# xkid_0_4.net
KiCad netlist of a schematic drawn in EAGLE
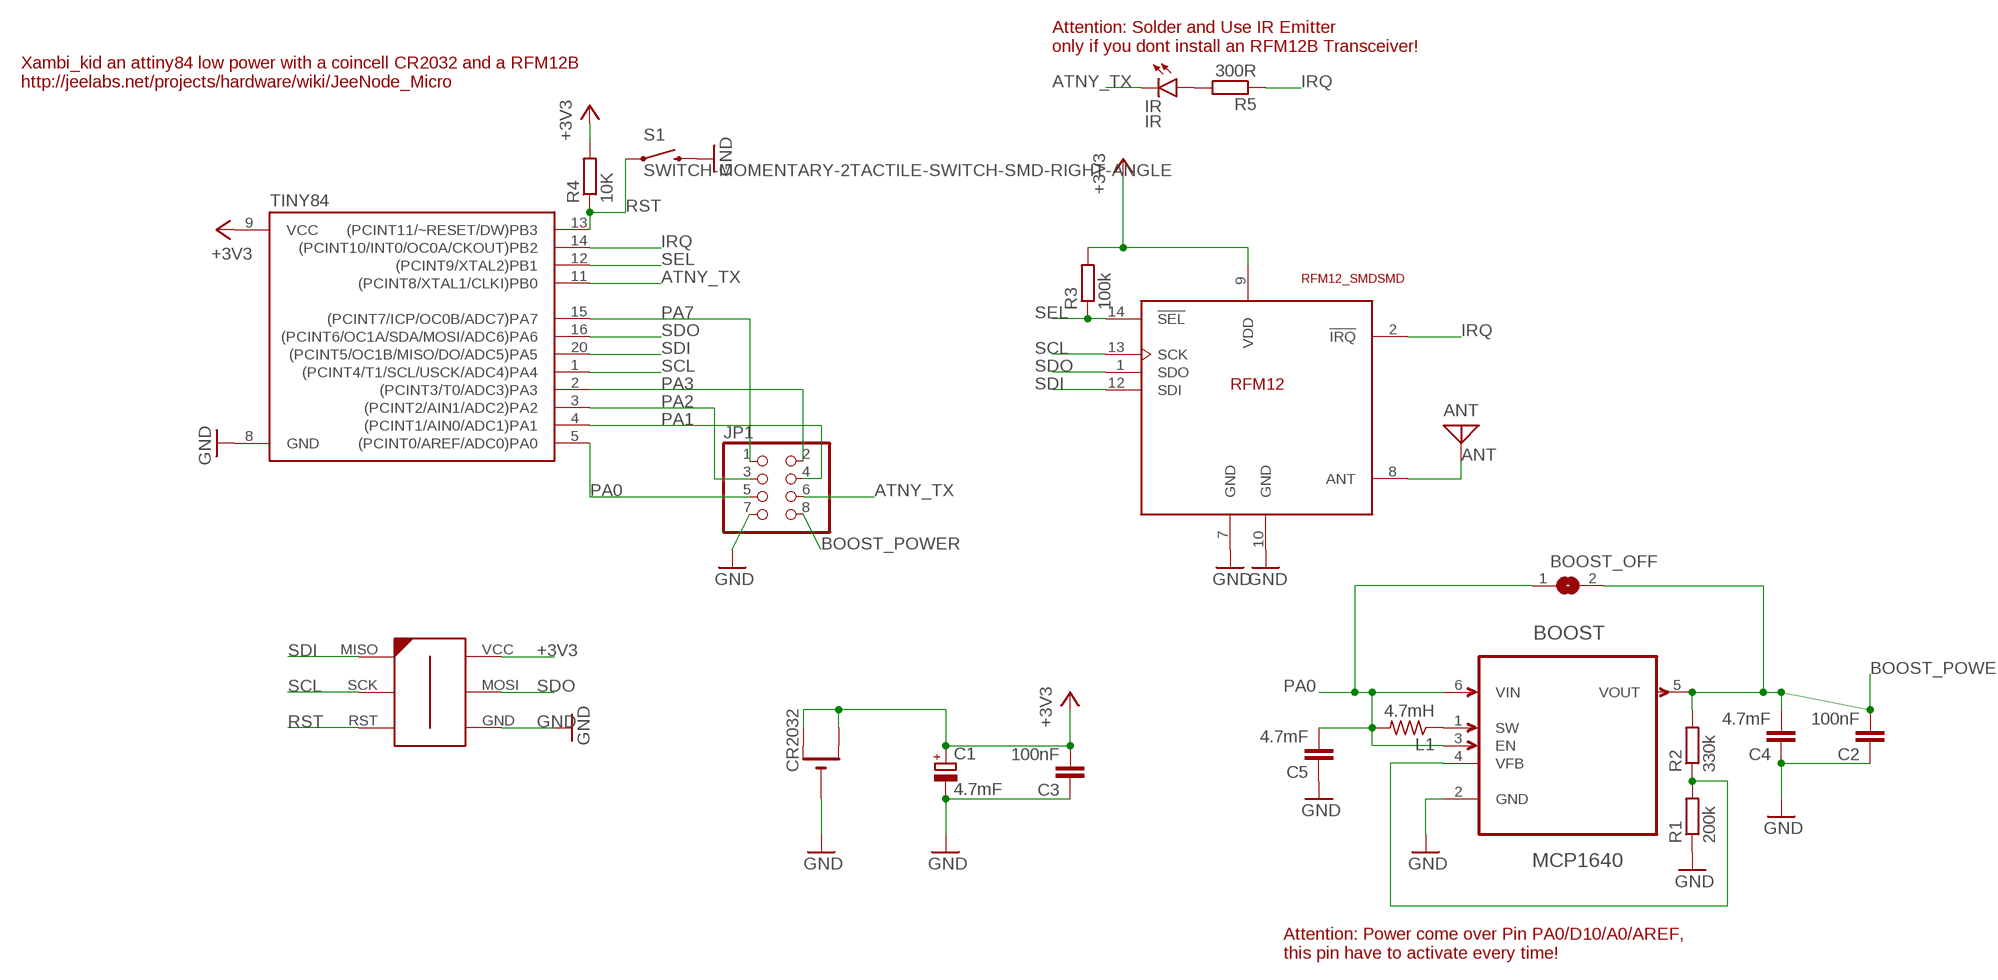
[diagram p0: schematic, sheet 1]

(export (version "E")
  (design (tool "Eeschema 10.0.6"))
  (components
    (comp (ref "ANT")
      (value "ANTENNA")
      (footprint "eagle-import:PAD-01")
      (libsource (lib "eagle-import") (part "ANTENNA"))
    )
    (comp (ref "BOOST")
      (value "MCP1640")
      (footprint "eagle-import:SOT95P270X145-6N")
      (fields (field (name "MPN") "MCP1640BT-I/CHY"))
      (libsource (lib "eagle-import") (part "MCP1640BT-I/CHY"))
    )
    (comp (ref "BOOST_OFF")
      (value "SJ")
      (footprint "eagle-import:SJ")
      (libsource (lib "eagle-import") (part "SJ"))
    )
    (comp (ref "C1")
      (value "4.7mF")
      (footprint "eagle-import:CT3216")
      (libsource (lib "eagle-import") (part "CPOL-EUCT3216"))
    )
    (comp (ref "C2")
      (value "100nF")
      (footprint "eagle-import:C0805K")
      (libsource (lib "eagle-import") (part "C-EUC0805K"))
    )
    (comp (ref "C3")
      (value "100nF")
      (footprint "eagle-import:C0805K")
      (libsource (lib "eagle-import") (part "C-EUC0805K"))
    )
    (comp (ref "C4")
      (value "4.7mF")
      (footprint "eagle-import:C0805K")
      (libsource (lib "eagle-import") (part "C-EUC0805K"))
    )
    (comp (ref "C5")
      (value "4.7mF")
      (footprint "eagle-import:C0805K")
      (libsource (lib "eagle-import") (part "C-EUC0805K"))
    )
    (comp (ref "CR2032")
      (value "CR2032SMT")
      (footprint "eagle-import:CR2032-SMD")
      (libsource (lib "eagle-import") (part "CR2032SMT"))
    )
    (comp (ref "IR")
      (value "IR")
      (footprint "eagle-import:LED3MM")
      (libsource (lib "eagle-import") (part "LED3MM"))
    )
    (comp (ref "JP1")
      (value "PINHD-2X4_2.54")
      (footprint "eagle-import:2X04")
      (libsource (lib "eagle-import") (part "PINHD-2X4_2.54"))
    )
    (comp (ref "L1")
      (value "4.7mH")
      (footprint "eagle-import:0204_5")
      (libsource (lib "eagle-import") (part "R-US_0204/5"))
    )
    (comp (ref "R1")
      (value "200k")
      (footprint "eagle-import:R0805")
      (libsource (lib "eagle-import") (part "R-EU_R0805"))
    )
    (comp (ref "R2")
      (value "330k")
      (footprint "eagle-import:R0805")
      (libsource (lib "eagle-import") (part "R-EU_R0805"))
    )
    (comp (ref "R3")
      (value "100k")
      (footprint "eagle-import:R0805")
      (libsource (lib "eagle-import") (part "R-EU_R0805"))
    )
    (comp (ref "R4")
      (value "10K")
      (footprint "eagle-import:R0805")
      (libsource (lib "eagle-import") (part "R-EU_R0805"))
    )
    (comp (ref "R5")
      (value "300R")
      (footprint "eagle-import:R0805")
      (libsource (lib "eagle-import") (part "R-EU_R0805"))
    )
    (comp (ref "S1")
      (value "SWITCH-MOMENTARY-2TACTILE-SWITCH-SMD-RIGHT-ANGLE")
      (footprint "eagle-import:TACTILE_SWITCH-SMD-RIGHT-ANGLE")
      (libsource (lib "eagle-import") (part "SWITCH-MOMENTARY-2TACTILE-SWITCH-SMD-RIGHT-ANGLE"))
    )
    (comp (ref "TINY84")
      (value "ATTINY84ATTINY84-20MU")
      (footprint "eagle-import:QFN20")
      (libsource (lib "eagle-import") (part "ATTINY84ATTINY84-20MU"))
    )
    (comp (ref "U$1")
      (value "RFM12_SMDSMD")
      (footprint "eagle-import:RFM12")
      (libsource (lib "eagle-import") (part "RFM12_SMDSMD"))
    )
    (comp (ref "U$2")
      (value "AVR-ISP-6-EDGE")
      (footprint "eagle-import:6PAD_ISP")
      (libsource (lib "eagle-import") (part "AVR-ISP-6-EDGE"))
    )
  )
  (nets
    (net (code "1") (name "+3V3") (class "Default")
      (node (ref "C1") (pin "+") (pinfunction "+_+") (pintype "passive"))
      (node (ref "C3") (pin "2") (pinfunction "2_2") (pintype "passive"))
      (node (ref "CR2032") (pin "+$1") (pinfunction "+_+$1") (pintype "passive"))
      (node (ref "CR2032") (pin "+$2") (pinfunction "+1_+$2") (pintype "passive"))
      (node (ref "R3") (pin "2") (pinfunction "2_2") (pintype "passive"))
      (node (ref "R4") (pin "2") (pinfunction "2_2") (pintype "passive"))
      (node (ref "TINY84") (pin "9") (pinfunction "VCC_9") (pintype "bidirectional"))
      (node (ref "U$1") (pin "9") (pinfunction "VDD_9") (pintype "power_in"))
      (node (ref "U$2") (pin "VCC") (pinfunction "P$6_VCC") (pintype "bidirectional"))
    )
    (net (code "2") (name "/ANT") (class "Default")
      (node (ref "ANT") (pin "1") (pinfunction "1_1") (pintype "output"))
      (node (ref "U$1") (pin "8") (pinfunction "ANT_8") (pintype "bidirectional"))
    )
    (net (code "3") (name "/ATNY_TX") (class "Default")
      (node (ref "IR") (pin "K") (pinfunction "C_K") (pintype "passive"))
      (node (ref "JP1") (pin "6") (pinfunction "6_6") (pintype "passive"))
      (node (ref "TINY84") (pin "11") (pinfunction "(PCINT8/XTAL1/CLKI)PB0_11") (pintype "bidirectional"))
    )
    (net (code "4") (name "/BOOST_POWER") (class "Default")
      (node (ref "BOOST") (pin "5") (pinfunction "VOUT_5") (pintype "output"))
      (node (ref "BOOST_OFF") (pin "2") (pinfunction "2_2") (pintype "passive"))
      (node (ref "C2") (pin "2") (pinfunction "2_2") (pintype "passive"))
      (node (ref "C4") (pin "2") (pinfunction "2_2") (pintype "passive"))
      (node (ref "JP1") (pin "8") (pinfunction "8_8") (pintype "passive"))
      (node (ref "R2") (pin "2") (pinfunction "2_2") (pintype "passive"))
    )
    (net (code "5") (name "/IRQ") (class "Default")
      (node (ref "R5") (pin "1") (pinfunction "1_1") (pintype "passive"))
      (node (ref "TINY84") (pin "14") (pinfunction "(PCINT10/INT0/OC0A/CKOUT)PB2_14") (pintype "bidirectional"))
      (node (ref "U$1") (pin "2") (pinfunction "~{IRQ}_2") (pintype "output"))
    )
    (net (code "6") (name "/PA0") (class "Default")
      (node (ref "BOOST") (pin "3") (pinfunction "EN_3") (pintype "input"))
      (node (ref "BOOST") (pin "6") (pinfunction "VIN_6") (pintype "input"))
      (node (ref "BOOST_OFF") (pin "1") (pinfunction "1_1") (pintype "passive"))
      (node (ref "C5") (pin "2") (pinfunction "2_2") (pintype "passive"))
      (node (ref "JP1") (pin "5") (pinfunction "5_5") (pintype "passive"))
      (node (ref "L1") (pin "2") (pinfunction "2_2") (pintype "passive"))
      (node (ref "TINY84") (pin "5") (pinfunction "(PCINT0/AREF/ADC0)PA0_5") (pintype "bidirectional"))
    )
    (net (code "7") (name "/PA1") (class "Default")
      (node (ref "JP1") (pin "4") (pinfunction "4_4") (pintype "passive"))
      (node (ref "TINY84") (pin "4") (pinfunction "(PCINT1/AIN0/ADC1)PA1_4") (pintype "bidirectional"))
    )
    (net (code "8") (name "/PA2") (class "Default")
      (node (ref "JP1") (pin "3") (pinfunction "3_3") (pintype "passive"))
      (node (ref "TINY84") (pin "3") (pinfunction "(PCINT2/AIN1/ADC2)PA2_3") (pintype "bidirectional"))
    )
    (net (code "9") (name "/PA3") (class "Default")
      (node (ref "JP1") (pin "2") (pinfunction "2_2") (pintype "passive"))
      (node (ref "TINY84") (pin "2") (pinfunction "(PCINT3/T0/ADC3)PA3_2") (pintype "bidirectional"))
    )
    (net (code "10") (name "/PA7") (class "Default")
      (node (ref "JP1") (pin "1") (pinfunction "1_1") (pintype "passive"))
      (node (ref "TINY84") (pin "15") (pinfunction "(PCINT7/ICP/OC0B/ADC7)PA7_15") (pintype "bidirectional"))
    )
    (net (code "11") (name "/RST") (class "Default")
      (node (ref "R4") (pin "1") (pinfunction "1_1") (pintype "passive"))
      (node (ref "S1") (pin "1") (pinfunction "1_1") (pintype "passive"))
      (node (ref "TINY84") (pin "13") (pinfunction "(PCINT11/~{RESET/DW})PB3_13") (pintype "bidirectional"))
      (node (ref "U$2") (pin "RST") (pinfunction "P$3_RST") (pintype "bidirectional"))
    )
    (net (code "12") (name "/SCL") (class "Default")
      (node (ref "TINY84") (pin "1") (pinfunction "(PCINT4/T1/SCL/USCK/ADC4)PA4_1") (pintype "bidirectional"))
      (node (ref "U$1") (pin "13") (pinfunction "SCK_13") (pintype "input"))
      (node (ref "U$2") (pin "SCK") (pinfunction "P$2_SCK") (pintype "bidirectional"))
    )
    (net (code "13") (name "/SDI") (class "Default")
      (node (ref "TINY84") (pin "20") (pinfunction "(PCINT5/OC1B/MISO/DO/ADC5)PA5_20") (pintype "bidirectional"))
      (node (ref "U$1") (pin "12") (pinfunction "SDI_12") (pintype "input"))
      (node (ref "U$2") (pin "MISO") (pinfunction "P$1_MISO") (pintype "bidirectional"))
    )
    (net (code "14") (name "/SDO") (class "Default")
      (node (ref "TINY84") (pin "16") (pinfunction "(PCINT6/OC1A/SDA/MOSI/ADC6)PA6_16") (pintype "bidirectional"))
      (node (ref "U$1") (pin "1") (pinfunction "SDO_1") (pintype "output"))
      (node (ref "U$2") (pin "MOSI") (pinfunction "P$5_MOSI") (pintype "bidirectional"))
    )
    (net (code "15") (name "/SEL") (class "Default")
      (node (ref "R3") (pin "1") (pinfunction "1_1") (pintype "passive"))
      (node (ref "TINY84") (pin "12") (pinfunction "(PCINT9/XTAL2)PB1_12") (pintype "bidirectional"))
      (node (ref "U$1") (pin "14") (pinfunction "~{SEL}_14") (pintype "input"))
    )
    (net (code "16") (name "GND") (class "Default")
      (node (ref "BOOST") (pin "2") (pinfunction "GND_2") (pintype "passive"))
      (node (ref "C1") (pin "-") (pinfunction "-_-") (pintype "passive"))
      (node (ref "C2") (pin "1") (pinfunction "1_1") (pintype "passive"))
      (node (ref "C3") (pin "1") (pinfunction "1_1") (pintype "passive"))
      (node (ref "C4") (pin "1") (pinfunction "1_1") (pintype "passive"))
      (node (ref "C5") (pin "1") (pinfunction "1_1") (pintype "passive"))
      (node (ref "CR2032") (pin "-") (pinfunction "-_-") (pintype "passive"))
      (node (ref "JP1") (pin "7") (pinfunction "7_7") (pintype "passive"))
      (node (ref "R1") (pin "1") (pinfunction "1_1") (pintype "passive"))
      (node (ref "S1") (pin "2") (pinfunction "2_2") (pintype "passive"))
      (node (ref "TINY84") (pin "8") (pinfunction "GND_8") (pintype "bidirectional"))
      (node (ref "U$1") (pin "10") (pinfunction "GND_10") (pintype "passive"))
      (node (ref "U$1") (pin "7") (pinfunction "GND_7") (pintype "passive"))
      (node (ref "U$2") (pin "GND") (pinfunction "P$4_GND") (pintype "bidirectional"))
    )
    (net (code "17") (name "Net-(BOOST-SW)") (class "Default")
      (node (ref "BOOST") (pin "1") (pinfunction "SW_1") (pintype "input"))
      (node (ref "L1") (pin "1") (pinfunction "1_1") (pintype "passive"))
    )
    (net (code "18") (name "Net-(BOOST-VFB)") (class "Default")
      (node (ref "BOOST") (pin "4") (pinfunction "VFB_4") (pintype "input"))
      (node (ref "R1") (pin "2") (pinfunction "2_2") (pintype "passive"))
      (node (ref "R2") (pin "1") (pinfunction "1_1") (pintype "passive"))
    )
    (net (code "19") (name "Net-(IR-PadA)") (class "Default")
      (node (ref "IR") (pin "A") (pinfunction "A_A") (pintype "passive"))
      (node (ref "R5") (pin "2") (pinfunction "2_2") (pintype "passive"))
    )
  )
)
